# NRF24L01.net
KiCad netlist of a schematic drawn in Altium Designer
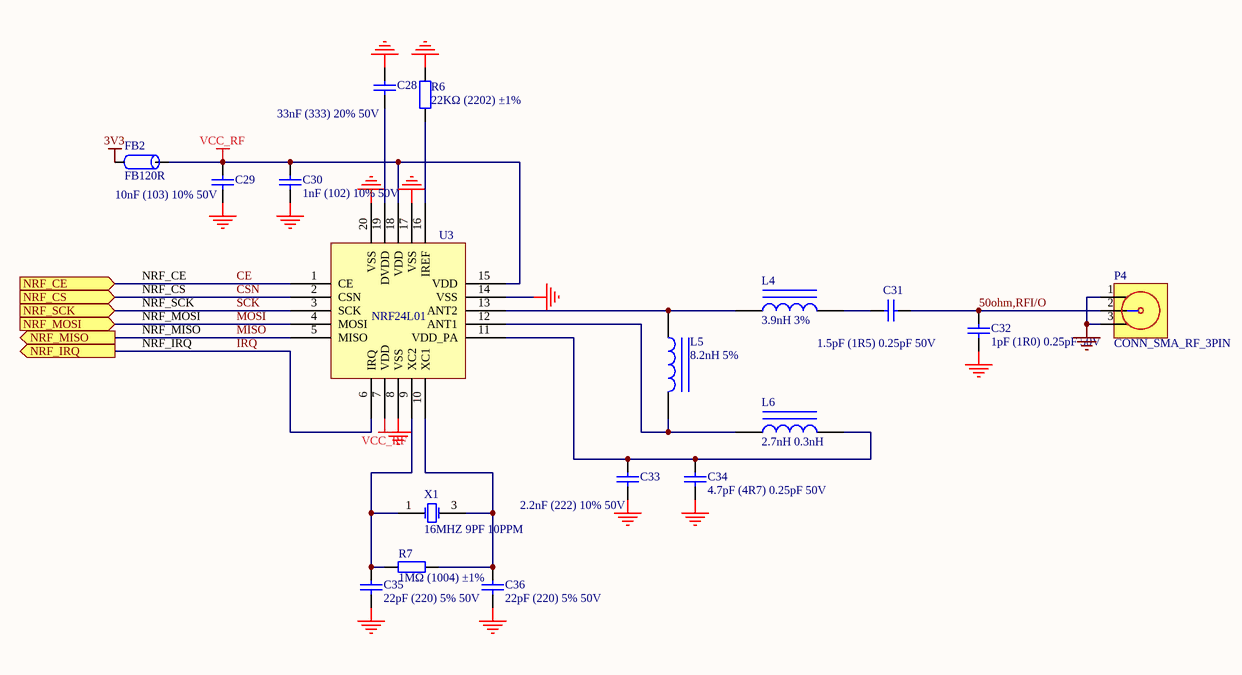
[diagram p0: NRF24L01.SchDoc]

(export (version "E")
  (design (tool "Eeschema 10.0.6"))
  (components
    (comp (ref "C28")
      (value "33nF (333) 20% 50V")
      (footprint "0402_C")
      (description "贴片电容")
      (libsource (lib "Miscellaneous Devices LC") (part "0402 33nF (333) 20% 50V"))
    )
    (comp (ref "C29")
      (value "10nF (103) 10% 50V")
      (footprint "0402_C")
      (description "贴片电容")
      (libsource (lib "Miscellaneous Devices LC") (part "0402 10nF (103) 10% 50V"))
    )
    (comp (ref "C30")
      (value "1nF (102) 10% 50V")
      (footprint "0402_C")
      (description "贴片电容")
      (libsource (lib "Miscellaneous Devices LC") (part "0402 1nF (102) 10% 50V"))
    )
    (comp (ref "C31")
      (value "1.5pF (1R5) 0.25pF 50V")
      (footprint "0402_C")
      (description "贴片电容")
      (libsource (lib "Miscellaneous Devices LC") (part "0402 1.5pF (1R5) 0.25pF 50V"))
    )
    (comp (ref "C32")
      (value "1pF (1R0) 0.25pF 50V")
      (footprint "0402_C")
      (description "贴片电容")
      (libsource (lib "Miscellaneous Devices LC") (part "0402 1pF (1R0) 0.25pF 50V"))
    )
    (comp (ref "C33")
      (value "2.2nF (222) 10% 50V")
      (footprint "0402_C")
      (description "贴片电容")
      (libsource (lib "Miscellaneous Devices LC") (part "0402 2.2nF (222) 10% 50V"))
    )
    (comp (ref "C34")
      (value "4.7pF (4R7) 0.25pF 50V")
      (footprint "0402_C")
      (description "贴片电容")
      (libsource (lib "Miscellaneous Devices LC") (part "0402 4.7pF (4R7) 0.25pF 50V"))
    )
    (comp (ref "C35")
      (value "22pF (220) 5% 50V")
      (footprint "0402_C")
      (description "贴片电容")
      (libsource (lib "Miscellaneous Devices LC") (part "0402 22pF (220) 5% 50V"))
    )
    (comp (ref "C36")
      (value "22pF (220) 5% 50V")
      (footprint "0402_C")
      (description "贴片电容")
      (libsource (lib "Miscellaneous Devices LC") (part "0402 22pF (220) 5% 50V"))
    )
    (comp (ref "FB2")
      (value "FB120R")
      (footprint "L0603")
      (description "贴片磁珠")
      (fields
        (field (name "MANUFACTURER") "TDK")
        (field (name "PART NUMBER") "RP02.99.000093")
        (field (name "PUBLISHER") "ChenYinaho")
      )
      (libsource (lib "tsl_Schlib") (part "FB_0603_120R"))
    )
    (comp (ref "L4")
      (value "3.9nH 3%")
      (footprint "0402_L")
      (description "贴片电感")
      (libsource (lib "Miscellaneous Devices LC") (part "0402 3.9nH 3%"))
    )
    (comp (ref "L5")
      (value "8.2nH 5%")
      (footprint "0402_L")
      (description "贴片电感")
      (libsource (lib "Miscellaneous Devices LC") (part "0402 8.2nH 5%"))
    )
    (comp (ref "L6")
      (value "2.7nH 0.3nH")
      (footprint "0402_L")
      (description "贴片电感")
      (libsource (lib "Miscellaneous Devices LC") (part "0402 2.7nH 0.3nH"))
    )
    (comp (ref "P4")
      (value "CONN_SMA_RF_3PIN")
      (footprint "PH_RF_2.5X2.5")
      (description "贴片天线座")
      (fields (field (name "PART NUMBER") "RP02.07.000078") (field (name "PUBLISHER") "ChenYinaho"))
      (libsource (lib "tsl_Schlib") (part "CONN_SMA_RF_3PIN"))
    )
    (comp (ref "R6")
      (value "22KΩ (2202) ±1%")
      (footprint "0402_R")
      (description "贴片电阻")
      (libsource (lib "Miscellaneous Devices LC") (part "0402 22KΩ (2202) 1%"))
    )
    (comp (ref "R7")
      (value "1MΩ (1004) ±1%")
      (footprint "0402_R")
      (description "贴片电阻")
      (libsource (lib "Miscellaneous Devices LC") (part "0402 1MΩ (1004) 1%"))
    )
    (comp (ref "U3") (value "NRF24L01") (footprint "QFN-20_4X4X05P") (libsource (lib "*") (part "NRF24L01")))
    (comp (ref "X1")
      (value "16MHZ 9PF 10PPM")
      (footprint "SMD-3225_4P")
      (description "贴片晶振")
      (libsource (lib "Miscellaneous Devices LC") (part "SMD-3225_4P  16MHZ 9PF 10PPM"))
    )
  )
  (nets
    (net (code "1") (name "/50ohm,RFI{slash}O") (class "Default")
      (node (ref "C31") (pin "2") (pinfunction "2_2") (pintype "passive"))
      (node (ref "C32") (pin "2") (pinfunction "2_2") (pintype "passive"))
      (node (ref "P4") (pin "2") (pintype "passive"))
    )
    (net (code "2") (name "/CE") (class "Default")
      (node (ref "U3") (pin "1") (pinfunction "CE_1") (pintype "passive"))
    )
    (net (code "3") (name "/CSN") (class "Default")
      (node (ref "U3") (pin "2") (pinfunction "CSN_2") (pintype "passive"))
    )
    (net (code "4") (name "/IRQ") (class "Default")
      (node (ref "U3") (pin "6") (pinfunction "IRQ_6") (pintype "passive"))
    )
    (net (code "5") (name "/MISO") (class "Default")
      (node (ref "U3") (pin "5") (pinfunction "MISO_5") (pintype "passive"))
    )
    (net (code "6") (name "/MOSI") (class "Default")
      (node (ref "U3") (pin "4") (pinfunction "MOSI_4") (pintype "passive"))
    )
    (net (code "7") (name "/NRF_SCK") (class "Default")
      (node (ref "U3") (pin "3") (pinfunction "SCK_3") (pintype "passive"))
    )
    (net (code "8") (name "3V3") (class "Default") (node (ref "FB2") (pin "2") (pintype "passive")))
    (net (code "9") (name "GND") (class "Default")
      (node (ref "C28") (pin "2") (pinfunction "2_2") (pintype "passive"))
      (node (ref "C29") (pin "1") (pinfunction "1_1") (pintype "passive"))
      (node (ref "C30") (pin "1") (pinfunction "1_1") (pintype "passive"))
      (node (ref "C32") (pin "1") (pinfunction "1_1") (pintype "passive"))
      (node (ref "C33") (pin "1") (pinfunction "1_1") (pintype "passive"))
      (node (ref "C34") (pin "1") (pinfunction "1_1") (pintype "passive"))
      (node (ref "C35") (pin "1") (pinfunction "1_1") (pintype "passive"))
      (node (ref "C36") (pin "1") (pinfunction "1_1") (pintype "passive"))
      (node (ref "P4") (pin "1") (pintype "passive"))
      (node (ref "P4") (pin "3") (pintype "passive"))
      (node (ref "R6") (pin "2") (pinfunction "2_2") (pintype "passive"))
      (node (ref "U3") (pin "14") (pinfunction "VSS_14") (pintype "passive"))
      (node (ref "U3") (pin "17") (pinfunction "VSS_17") (pintype "passive"))
      (node (ref "U3") (pin "20") (pinfunction "VSS_20") (pintype "passive"))
      (node (ref "U3") (pin "8") (pinfunction "VSS_8") (pintype "passive"))
    )
    (net (code "10") (name "Net-(C31-Pad1)") (class "Default")
      (node (ref "C31") (pin "1") (pinfunction "1_1") (pintype "passive"))
      (node (ref "L4") (pin "2") (pinfunction "2_2") (pintype "passive"))
    )
    (net (code "11") (name "Net-(U3-ANT1)") (class "Default")
      (node (ref "L5") (pin "2") (pinfunction "2_2") (pintype "passive"))
      (node (ref "L6") (pin "1") (pinfunction "1_1") (pintype "passive"))
      (node (ref "U3") (pin "12") (pinfunction "ANT1_12") (pintype "passive"))
    )
    (net (code "12") (name "Net-(U3-ANT2)") (class "Default")
      (node (ref "L4") (pin "1") (pinfunction "1_1") (pintype "passive"))
      (node (ref "L5") (pin "1") (pinfunction "1_1") (pintype "passive"))
      (node (ref "U3") (pin "13") (pinfunction "ANT2_13") (pintype "passive"))
    )
    (net (code "13") (name "Net-(U3-DVDD)") (class "Default")
      (node (ref "C28") (pin "1") (pinfunction "1_1") (pintype "passive"))
      (node (ref "U3") (pin "19") (pinfunction "DVDD_19") (pintype "passive"))
    )
    (net (code "14") (name "Net-(U3-IREF)") (class "Default")
      (node (ref "R6") (pin "1") (pinfunction "1_1") (pintype "passive"))
      (node (ref "U3") (pin "16") (pinfunction "IREF_16") (pintype "passive"))
    )
    (net (code "15") (name "Net-(U3-VDD_PA)") (class "Default")
      (node (ref "C33") (pin "2") (pinfunction "2_2") (pintype "passive"))
      (node (ref "C34") (pin "2") (pinfunction "2_2") (pintype "passive"))
      (node (ref "L6") (pin "2") (pinfunction "2_2") (pintype "passive"))
      (node (ref "U3") (pin "11") (pinfunction "VDD_PA_11") (pintype "passive"))
    )
    (net (code "16") (name "Net-(U3-XC1)") (class "Default")
      (node (ref "C36") (pin "2") (pinfunction "2_2") (pintype "passive"))
      (node (ref "R7") (pin "2") (pinfunction "2_2") (pintype "passive"))
      (node (ref "U3") (pin "10") (pinfunction "XC1_10") (pintype "passive"))
      (node (ref "X1") (pin "3") (pinfunction "OSC2_3") (pintype "passive"))
    )
    (net (code "17") (name "Net-(U3-XC2)") (class "Default")
      (node (ref "C35") (pin "2") (pinfunction "2_2") (pintype "passive"))
      (node (ref "R7") (pin "1") (pinfunction "1_1") (pintype "passive"))
      (node (ref "U3") (pin "9") (pinfunction "XC2_9") (pintype "passive"))
      (node (ref "X1") (pin "1") (pinfunction "OSC1_1") (pintype "passive"))
    )
    (net (code "18") (name "VCC_RF") (class "Default")
      (node (ref "C29") (pin "2") (pinfunction "2_2") (pintype "passive"))
      (node (ref "C30") (pin "2") (pinfunction "2_2") (pintype "passive"))
      (node (ref "FB2") (pin "1") (pintype "passive"))
      (node (ref "U3") (pin "15") (pinfunction "VDD_15") (pintype "passive"))
      (node (ref "U3") (pin "18") (pinfunction "VDD_18") (pintype "passive"))
      (node (ref "U3") (pin "7") (pinfunction "VDD_7") (pintype "passive"))
    )
  )
)
